# openfc.net
KiCad netlist of a schematic drawn in EAGLE
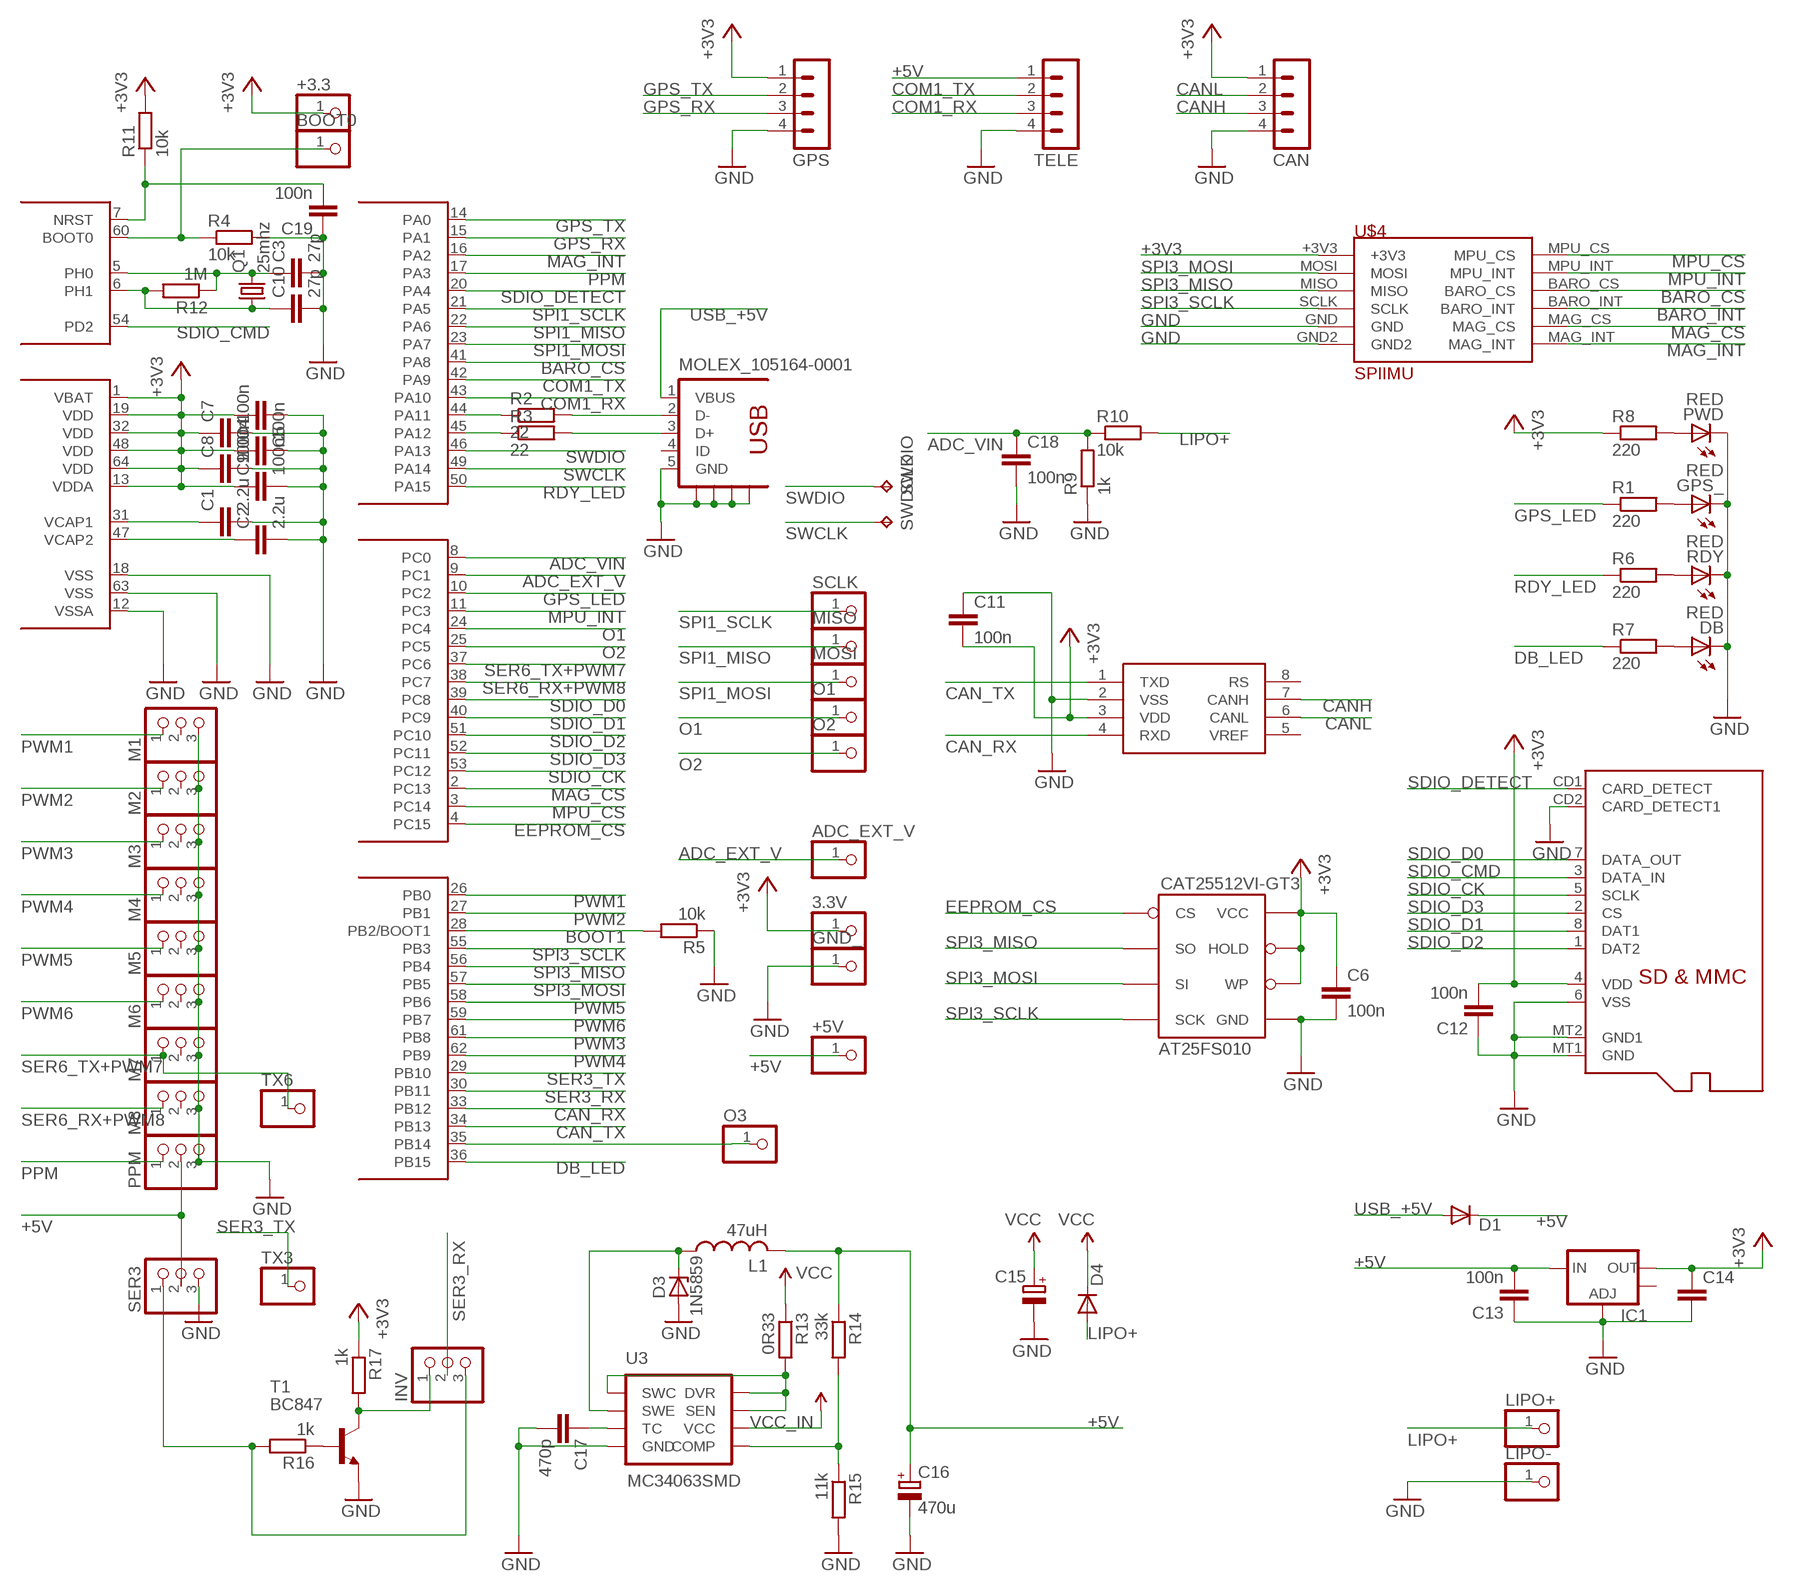
[diagram p0: schematic, sheet 1]

(export (version "E")
  (design (tool "Eeschema 10.0.6"))
  (components
    (comp (ref "+3.3")
      (value "PINHD-1X1")
      (footprint "eagle-import:1X01")
      (libsource (lib "eagle-import") (part "PINHD-1X1"))
    )
    (comp (ref "+5V")
      (value "PINHD-1X1")
      (footprint "eagle-import:1X01")
      (libsource (lib "eagle-import") (part "PINHD-1X1"))
    )
    (comp (ref "3.3V")
      (value "PINHD-1X1")
      (footprint "eagle-import:1X01")
      (libsource (lib "eagle-import") (part "PINHD-1X1"))
    )
    (comp (ref "ADC_EXT_V")
      (value "PINHD-1X1")
      (footprint "eagle-import:1X01")
      (libsource (lib "eagle-import") (part "PINHD-1X1"))
    )
    (comp (ref "BOOT0")
      (value "PINHD-1X1")
      (footprint "eagle-import:1X01")
      (libsource (lib "eagle-import") (part "PINHD-1X1"))
    )
    (comp (ref "C1")
      (value "2.2u")
      (footprint "eagle-import:C0603")
      (libsource (lib "eagle-import") (part "C-EUC0603"))
    )
    (comp (ref "C2")
      (value "2.2u")
      (footprint "eagle-import:C0603")
      (libsource (lib "eagle-import") (part "C-EUC0603"))
    )
    (comp (ref "C3")
      (value "27p")
      (footprint "eagle-import:C0603")
      (libsource (lib "eagle-import") (part "C-EUC0603"))
    )
    (comp (ref "C4")
      (value "100n")
      (footprint "eagle-import:C0603")
      (libsource (lib "eagle-import") (part "C-EUC0603"))
    )
    (comp (ref "C5")
      (value "100n")
      (footprint "eagle-import:C0603")
      (libsource (lib "eagle-import") (part "C-EUC0603"))
    )
    (comp (ref "C6")
      (value "100n")
      (footprint "eagle-import:C0603")
      (libsource (lib "eagle-import") (part "C-EUC0603"))
    )
    (comp (ref "C7")
      (value "100n")
      (footprint "eagle-import:C0603")
      (libsource (lib "eagle-import") (part "C-EUC0603"))
    )
    (comp (ref "C8")
      (value "100n")
      (footprint "eagle-import:C0603")
      (libsource (lib "eagle-import") (part "C-EUC0603"))
    )
    (comp (ref "C9")
      (value "100n")
      (footprint "eagle-import:C0603")
      (libsource (lib "eagle-import") (part "C-EUC0603"))
    )
    (comp (ref "C10")
      (value "27p")
      (footprint "eagle-import:C0603")
      (libsource (lib "eagle-import") (part "C-EUC0603"))
    )
    (comp (ref "C11")
      (value "100n")
      (footprint "eagle-import:C0603")
      (libsource (lib "eagle-import") (part "C-EUC0603"))
    )
    (comp (ref "C12")
      (value "100n")
      (footprint "eagle-import:C0603")
      (libsource (lib "eagle-import") (part "C-EUC0603"))
    )
    (comp (ref "C13")
      (value "100n")
      (footprint "eagle-import:C0603")
      (libsource (lib "eagle-import") (part "C-EUC0603"))
    )
    (comp (ref "C14")
      (value "C-EUC1206")
      (footprint "eagle-import:C1206")
      (libsource (lib "eagle-import") (part "C-EUC1206"))
    )
    (comp (ref "C15")
      (value "CPOL-EUB/3528-21R")
      (footprint "eagle-import:B_3528-21R")
      (libsource (lib "eagle-import") (part "CPOL-EUB/3528-21R"))
    )
    (comp (ref "C16")
      (value "470u")
      (footprint "eagle-import:B_3528-21R")
      (libsource (lib "eagle-import") (part "CPOL-EUB/3528-21R"))
    )
    (comp (ref "C17")
      (value "470p")
      (footprint "eagle-import:C0603")
      (libsource (lib "eagle-import") (part "C-EUC0603"))
    )
    (comp (ref "C18")
      (value "100n")
      (footprint "eagle-import:C0603")
      (libsource (lib "eagle-import") (part "C-EUC0603"))
    )
    (comp (ref "C19")
      (value "100n")
      (footprint "eagle-import:C0603")
      (libsource (lib "eagle-import") (part "C-EUC0603"))
    )
    (comp (ref "CAN")
      (value "MA04-1")
      (footprint "eagle-import:MA04-1")
      (fields (field (name "OC_FARNELL") "unknown") (field (name "OC_NEWARK") "unknown"))
      (libsource (lib "eagle-import") (part "MA04-1"))
    )
    (comp (ref "CAT25512VI-GT3")
      (value "AT25FS010")
      (footprint "eagle-import:SO08WIDE")
      (libsource (lib "eagle-import") (part "AT25FS010"))
    )
    (comp (ref "D1")
      (value "DIODE-SMB")
      (footprint "eagle-import:SMB")
      (libsource (lib "eagle-import") (part "DIODE-SMB"))
    )
    (comp (ref "D3")
      (value "1N5859")
      (footprint "eagle-import:SMB")
      (libsource (lib "eagle-import") (part "ZENER-DIODESMB"))
    )
    (comp (ref "D4")
      (value "DIODE-SMB")
      (footprint "eagle-import:SMB")
      (libsource (lib "eagle-import") (part "DIODE-SMB"))
    )
    (comp (ref "DB")
      (value "RED")
      (footprint "eagle-import:LED-0603")
      (fields (field (name "PROD_ID") "DIO-00819"))
      (libsource (lib "eagle-import") (part "LED-RED0603"))
    )
    (comp (ref "GND_")
      (value "PINHD-1X1")
      (footprint "eagle-import:1X01")
      (libsource (lib "eagle-import") (part "PINHD-1X1"))
    )
    (comp (ref "GPS")
      (value "MA04-1")
      (footprint "eagle-import:MA04-1")
      (libsource (lib "eagle-import") (part "MA04-1"))
    )
    (comp (ref "GPS_")
      (value "RED")
      (footprint "eagle-import:LED-0603")
      (fields (field (name "PROD_ID") "DIO-00819"))
      (libsource (lib "eagle-import") (part "LED-RED0603"))
    )
    (comp (ref "IC1")
      (value "V_REG_LM1117SOT223")
      (footprint "eagle-import:SOT223")
      (libsource (lib "eagle-import") (part "V_REG_LM1117SOT223"))
    )
    (comp (ref "INV")
      (value "PINHD-1X3")
      (footprint "eagle-import:1X03")
      (libsource (lib "eagle-import") (part "PINHD-1X3"))
    )
    (comp (ref "L1")
      (value "47uH")
      (footprint "eagle-import:L1812")
      (libsource (lib "eagle-import") (part "L-USL1812"))
    )
    (comp (ref "LIPO+")
      (value "PINHD-1X1")
      (footprint "eagle-import:1X01")
      (libsource (lib "eagle-import") (part "PINHD-1X1"))
    )
    (comp (ref "LIPO-")
      (value "PINHD-1X1")
      (footprint "eagle-import:1X01")
      (libsource (lib "eagle-import") (part "PINHD-1X1"))
    )
    (comp (ref "M1")
      (value "PINHD-1X3")
      (footprint "eagle-import:1X03")
      (libsource (lib "eagle-import") (part "PINHD-1X3"))
    )
    (comp (ref "M2")
      (value "PINHD-1X3")
      (footprint "eagle-import:1X03")
      (libsource (lib "eagle-import") (part "PINHD-1X3"))
    )
    (comp (ref "M3")
      (value "PINHD-1X3")
      (footprint "eagle-import:1X03")
      (libsource (lib "eagle-import") (part "PINHD-1X3"))
    )
    (comp (ref "M4")
      (value "PINHD-1X3")
      (footprint "eagle-import:1X03")
      (libsource (lib "eagle-import") (part "PINHD-1X3"))
    )
    (comp (ref "M5")
      (value "PINHD-1X3")
      (footprint "eagle-import:1X03")
      (libsource (lib "eagle-import") (part "PINHD-1X3"))
    )
    (comp (ref "M6")
      (value "PINHD-1X3")
      (footprint "eagle-import:1X03")
      (libsource (lib "eagle-import") (part "PINHD-1X3"))
    )
    (comp (ref "M7")
      (value "PINHD-1X3")
      (footprint "eagle-import:1X03")
      (libsource (lib "eagle-import") (part "PINHD-1X3"))
    )
    (comp (ref "M8")
      (value "PINHD-1X3")
      (footprint "eagle-import:1X03")
      (libsource (lib "eagle-import") (part "PINHD-1X3"))
    )
    (comp (ref "MISO")
      (value "PINHD-1X1")
      (footprint "eagle-import:1X01")
      (libsource (lib "eagle-import") (part "PINHD-1X1"))
    )
    (comp (ref "MOLEX_47334-0001")
      (value "MICROSD")
      (footprint "eagle-import:MICROSD")
      (libsource (lib "eagle-import") (part "MICROSD"))
    )
    (comp (ref "MOLEX_105164-0001")
      (value "USB-5P")
      (footprint "eagle-import:USB-MINI-B")
      (libsource (lib "eagle-import") (part "USB-5P"))
    )
    (comp (ref "MOSI")
      (value "PINHD-1X1")
      (footprint "eagle-import:1X01")
      (libsource (lib "eagle-import") (part "PINHD-1X1"))
    )
    (comp (ref "O1")
      (value "PINHD-1X1")
      (footprint "eagle-import:1X01")
      (libsource (lib "eagle-import") (part "PINHD-1X1"))
    )
    (comp (ref "O2")
      (value "PINHD-1X1")
      (footprint "eagle-import:1X01")
      (libsource (lib "eagle-import") (part "PINHD-1X1"))
    )
    (comp (ref "O3")
      (value "PINHD-1X1")
      (footprint "eagle-import:1X01")
      (libsource (lib "eagle-import") (part "PINHD-1X1"))
    )
    (comp (ref "PPM")
      (value "PINHD-1X3")
      (footprint "eagle-import:1X03")
      (libsource (lib "eagle-import") (part "PINHD-1X3"))
    )
    (comp (ref "PWD")
      (value "RED")
      (footprint "eagle-import:LED-0603")
      (fields (field (name "PROD_ID") "DIO-00819"))
      (libsource (lib "eagle-import") (part "LED-RED0603"))
    )
    (comp (ref "Q1")
      (value "25mhz")
      (footprint "eagle-import:CTS406")
      (fields (field (name "OC_FARNELL") "unknown"))
      (libsource (lib "eagle-import") (part "CRYSTALCTS406"))
    )
    (comp (ref "R1")
      (value "220")
      (footprint "eagle-import:R0603")
      (libsource (lib "eagle-import") (part "R-EU_R0603"))
    )
    (comp (ref "R2")
      (value "22")
      (footprint "eagle-import:R0603")
      (libsource (lib "eagle-import") (part "R-EU_R0603"))
    )
    (comp (ref "R3")
      (value "22")
      (footprint "eagle-import:R0603")
      (libsource (lib "eagle-import") (part "R-EU_R0603"))
    )
    (comp (ref "R4")
      (value "10k")
      (footprint "eagle-import:R0603")
      (libsource (lib "eagle-import") (part "R-EU_R0603"))
    )
    (comp (ref "R5")
      (value "10k")
      (footprint "eagle-import:R0603")
      (libsource (lib "eagle-import") (part "R-EU_R0603"))
    )
    (comp (ref "R6")
      (value "220")
      (footprint "eagle-import:R0603")
      (libsource (lib "eagle-import") (part "R-EU_R0603"))
    )
    (comp (ref "R7")
      (value "220")
      (footprint "eagle-import:R0603")
      (libsource (lib "eagle-import") (part "R-EU_R0603"))
    )
    (comp (ref "R8")
      (value "220")
      (footprint "eagle-import:R0603")
      (libsource (lib "eagle-import") (part "R-EU_R0603"))
    )
    (comp (ref "R9")
      (value "1k")
      (footprint "eagle-import:R0603")
      (libsource (lib "eagle-import") (part "R-EU_R0603"))
    )
    (comp (ref "R10")
      (value "10k")
      (footprint "eagle-import:R0603")
      (libsource (lib "eagle-import") (part "R-EU_R0603"))
    )
    (comp (ref "R11")
      (value "10k")
      (footprint "eagle-import:R0603")
      (libsource (lib "eagle-import") (part "R-EU_R0603"))
    )
    (comp (ref "R12")
      (value "1M")
      (footprint "eagle-import:R0603")
      (libsource (lib "eagle-import") (part "R-EU_R0603"))
    )
    (comp (ref "R13")
      (value "0R33")
      (footprint "eagle-import:R0603")
      (libsource (lib "eagle-import") (part "R-EU_R0603"))
    )
    (comp (ref "R14")
      (value "33k")
      (footprint "eagle-import:R0603")
      (libsource (lib "eagle-import") (part "R-EU_R0603"))
    )
    (comp (ref "R15")
      (value "11k")
      (footprint "eagle-import:R0603")
      (libsource (lib "eagle-import") (part "R-EU_R0603"))
    )
    (comp (ref "R16")
      (value "1k")
      (footprint "eagle-import:R0603")
      (libsource (lib "eagle-import") (part "R-EU_R0603"))
    )
    (comp (ref "R17")
      (value "1k")
      (footprint "eagle-import:R0603")
      (libsource (lib "eagle-import") (part "R-EU_R0603"))
    )
    (comp (ref "RDY")
      (value "RED")
      (footprint "eagle-import:LED-0603")
      (fields (field (name "PROD_ID") "DIO-00819"))
      (libsource (lib "eagle-import") (part "LED-RED0603"))
    )
    (comp (ref "SCLK")
      (value "PINHD-1X1")
      (footprint "eagle-import:1X01")
      (libsource (lib "eagle-import") (part "PINHD-1X1"))
    )
    (comp (ref "SER3")
      (value "PINHD-1X3")
      (footprint "eagle-import:1X03")
      (libsource (lib "eagle-import") (part "PINHD-1X3"))
    )
    (comp (ref "SWDCLK")
      (value "TPTP14SQ")
      (footprint "eagle-import:TP14SQ")
      (libsource (lib "eagle-import") (part "TPTP14SQ"))
    )
    (comp (ref "SWDIO")
      (value "TPTP14SQ")
      (footprint "eagle-import:TP14SQ")
      (libsource (lib "eagle-import") (part "TPTP14SQ"))
    )
    (comp (ref "T1")
      (value "BC847")
      (footprint "eagle-import:SOT23")
      (libsource (lib "eagle-import") (part "BC847"))
    )
    (comp (ref "TELE")
      (value "MA04-1")
      (footprint "eagle-import:MA04-1")
      (libsource (lib "eagle-import") (part "MA04-1"))
    )
    (comp (ref "TX3")
      (value "PINHD-1X1")
      (footprint "eagle-import:1X01")
      (libsource (lib "eagle-import") (part "PINHD-1X1"))
    )
    (comp (ref "TX6")
      (value "PINHD-1X1")
      (footprint "eagle-import:1X01")
      (libsource (lib "eagle-import") (part "PINHD-1X1"))
    )
    (comp (ref "U$4")
      (value "SPIIMU")
      (footprint "eagle-import:SPIIMU")
      (libsource (lib "eagle-import") (part "SPIIMU"))
    )
    (comp (ref "U1")
      (value "STM32F4-64")
      (footprint "eagle-import:SQFP-S-10X10-64")
      (libsource (lib "eagle-import") (part "STM32F4-64"))
    )
    (comp (ref "U3")
      (value "MC34063SMD")
      (footprint "eagle-import:SO08")
      (libsource (lib "eagle-import") (part "MC34063SMD"))
    )
    (comp (ref "U4")
      (value "MCP2551")
      (footprint "eagle-import:SO08")
      (libsource (lib "eagle-import") (part "MCP2551"))
    )
  )
  (nets
    (net (code "1") (name "+3V3") (class "Default")
      (node (ref "+3.3") (pin "1") (pinfunction "1_1") (pintype "passive"))
      (node (ref "3.3V") (pin "1") (pinfunction "1_1") (pintype "passive"))
      (node (ref "C11") (pin "2") (pinfunction "2_2") (pintype "passive"))
      (node (ref "C12") (pin "2") (pinfunction "2_2") (pintype "passive"))
      (node (ref "C14") (pin "1") (pinfunction "1_1") (pintype "passive"))
      (node (ref "C4") (pin "1") (pinfunction "1_1") (pintype "passive"))
      (node (ref "C5") (pin "2") (pinfunction "2_2") (pintype "passive"))
      (node (ref "C6") (pin "1") (pinfunction "1_1") (pintype "passive"))
      (node (ref "C7") (pin "1") (pinfunction "1_1") (pintype "passive"))
      (node (ref "C8") (pin "1") (pinfunction "1_1") (pintype "passive"))
      (node (ref "C9") (pin "1") (pinfunction "1_1") (pintype "passive"))
      (node (ref "CAN") (pin "1") (pinfunction "1_1") (pintype "passive"))
      (node (ref "CAT25512VI-GT3") (pin "3") (pinfunction "WP_3") (pintype "bidirectional"))
      (node (ref "CAT25512VI-GT3") (pin "7") (pinfunction "HOLD_7") (pintype "bidirectional"))
      (node (ref "CAT25512VI-GT3") (pin "8") (pinfunction "VCC_8") (pintype "bidirectional"))
      (node (ref "GPS") (pin "1") (pinfunction "1_1") (pintype "passive"))
      (node (ref "IC1") (pin "2") (pinfunction "OUT_2") (pintype "output"))
      (node (ref "MOLEX_47334-0001") (pin "4") (pinfunction "VDD_4") (pintype "power_in"))
      (node (ref "R11") (pin "2") (pinfunction "2_2") (pintype "passive"))
      (node (ref "R17") (pin "1") (pinfunction "1_1") (pintype "passive"))
      (node (ref "R8") (pin "1") (pinfunction "1_1") (pintype "passive"))
      (node (ref "U$4") (pin "+3V3") (pinfunction "+3V3_+3V3") (pintype "power_in"))
      (node (ref "U1") (pin "1") (pinfunction "VBAT_1") (pintype "power_in"))
      (node (ref "U1") (pin "13") (pinfunction "VDDA_13") (pintype "power_in"))
      (node (ref "U1") (pin "19") (pinfunction "VDD_19") (pintype "power_in"))
      (node (ref "U1") (pin "32") (pinfunction "VDD_32") (pintype "power_in"))
      (node (ref "U1") (pin "48") (pinfunction "VDD_48") (pintype "power_in"))
      (node (ref "U1") (pin "64") (pinfunction "VDD_64") (pintype "power_in"))
      (node (ref "U4") (pin "3") (pinfunction "VDD_3") (pintype "bidirectional"))
    )
    (net (code "2") (name "/+5V") (class "Default")
      (node (ref "+5V") (pin "1") (pinfunction "1_1") (pintype "passive"))
      (node (ref "C13") (pin "2") (pinfunction "2_2") (pintype "passive"))
      (node (ref "C16") (pin "+") (pinfunction "+_+") (pintype "passive"))
      (node (ref "D1") (pin "C") (pinfunction "C_C") (pintype "passive"))
      (node (ref "IC1") (pin "3") (pinfunction "IN_3") (pintype "input"))
      (node (ref "L1") (pin "2") (pinfunction "2_2") (pintype "passive"))
      (node (ref "PPM") (pin "2") (pinfunction "2_2") (pintype "passive"))
      (node (ref "R14") (pin "1") (pinfunction "1_1") (pintype "passive"))
      (node (ref "SER3") (pin "2") (pinfunction "2_2") (pintype "passive"))
      (node (ref "TELE") (pin "1") (pinfunction "1_1") (pintype "passive"))
    )
    (net (code "3") (name "/ADC_EXT_V") (class "Default")
      (node (ref "ADC_EXT_V") (pin "1") (pinfunction "1_1") (pintype "passive"))
      (node (ref "U1") (pin "9") (pinfunction "PC1_9") (pintype "bidirectional"))
    )
    (net (code "4") (name "/ADC_VIN") (class "Default")
      (node (ref "C18") (pin "1") (pinfunction "1_1") (pintype "passive"))
      (node (ref "R10") (pin "1") (pinfunction "1_1") (pintype "passive"))
      (node (ref "R9") (pin "2") (pinfunction "2_2") (pintype "passive"))
      (node (ref "U1") (pin "8") (pinfunction "PC0_8") (pintype "bidirectional"))
    )
    (net (code "5") (name "/BARO_CS") (class "Default")
      (node (ref "U$4") (pin "BARO_CS") (pinfunction "BARO_CS_BARO_CS") (pintype "bidirectional"))
      (node (ref "U1") (pin "41") (pinfunction "PA8_41") (pintype "bidirectional"))
    )
    (net (code "6") (name "/BARO_INT") (class "Default")
      (node (ref "U$4") (pin "BARO_INT") (pinfunction "BARO_INT_BARO_INT") (pintype "bidirectional"))
    )
    (net (code "7") (name "/BOOT1") (class "Default")
      (node (ref "R5") (pin "2") (pinfunction "2_2") (pintype "passive"))
      (node (ref "U1") (pin "28") (pinfunction "PB2/BOOT1_28") (pintype "bidirectional"))
    )
    (net (code "8") (name "/CANH") (class "Default")
      (node (ref "CAN") (pin "3") (pinfunction "3_3") (pintype "passive"))
      (node (ref "U4") (pin "7") (pinfunction "CANH_7") (pintype "bidirectional"))
    )
    (net (code "9") (name "/CANL") (class "Default")
      (node (ref "CAN") (pin "2") (pinfunction "2_2") (pintype "passive"))
      (node (ref "U4") (pin "6") (pinfunction "CANL_6") (pintype "bidirectional"))
    )
    (net (code "10") (name "/CAN_RX") (class "Default")
      (node (ref "U1") (pin "33") (pinfunction "PB12_33") (pintype "bidirectional"))
      (node (ref "U4") (pin "4") (pinfunction "RXD_4") (pintype "bidirectional"))
    )
    (net (code "11") (name "/CAN_TX") (class "Default")
      (node (ref "U1") (pin "34") (pinfunction "PB13_34") (pintype "bidirectional"))
      (node (ref "U4") (pin "1") (pinfunction "TXD_1") (pintype "bidirectional"))
    )
    (net (code "12") (name "/COM1_RX") (class "Default")
      (node (ref "TELE") (pin "3") (pinfunction "3_3") (pintype "passive"))
      (node (ref "U1") (pin "43") (pinfunction "PA10_43") (pintype "bidirectional"))
    )
    (net (code "13") (name "/COM1_TX") (class "Default")
      (node (ref "TELE") (pin "2") (pinfunction "2_2") (pintype "passive"))
      (node (ref "U1") (pin "42") (pinfunction "PA9_42") (pintype "bidirectional"))
    )
    (net (code "14") (name "/DB_LED") (class "Default")
      (node (ref "R7") (pin "1") (pinfunction "1_1") (pintype "passive"))
      (node (ref "U1") (pin "36") (pinfunction "PB15_36") (pintype "bidirectional"))
    )
    (net (code "15") (name "/EEPROM_CS") (class "Default")
      (node (ref "CAT25512VI-GT3") (pin "1") (pinfunction "CS_1") (pintype "bidirectional"))
      (node (ref "U1") (pin "4") (pinfunction "PC15_4") (pintype "bidirectional"))
    )
    (net (code "16") (name "/GPS_LED") (class "Default")
      (node (ref "R1") (pin "1") (pinfunction "1_1") (pintype "passive"))
      (node (ref "U1") (pin "10") (pinfunction "PC2_10") (pintype "bidirectional"))
    )
    (net (code "17") (name "/GPS_RX") (class "Default")
      (node (ref "GPS") (pin "3") (pinfunction "3_3") (pintype "passive"))
      (node (ref "U1") (pin "15") (pinfunction "PA1_15") (pintype "bidirectional"))
    )
    (net (code "18") (name "/GPS_TX") (class "Default")
      (node (ref "GPS") (pin "2") (pinfunction "2_2") (pintype "passive"))
      (node (ref "U1") (pin "14") (pinfunction "PA0_14") (pintype "bidirectional"))
    )
    (net (code "19") (name "/LIPO+") (class "Default")
      (node (ref "D4") (pin "A") (pinfunction "A_A") (pintype "passive"))
      (node (ref "LIPO+") (pin "1") (pinfunction "1_1") (pintype "passive"))
      (node (ref "R10") (pin "2") (pinfunction "2_2") (pintype "passive"))
    )
    (net (code "20") (name "/MAG_CS") (class "Default")
      (node (ref "U$4") (pin "MAG_CS") (pinfunction "MAG_CS_MAG_CS") (pintype "bidirectional"))
      (node (ref "U1") (pin "2") (pinfunction "PC13_2") (pintype "bidirectional"))
    )
    (net (code "21") (name "/MAG_INT") (class "Default")
      (node (ref "U$4") (pin "MAG_INT") (pinfunction "MAG_INT_MAG_INT") (pintype "bidirectional"))
      (node (ref "U1") (pin "16") (pinfunction "PA2_16") (pintype "bidirectional"))
    )
    (net (code "22") (name "/MPU_CS") (class "Default")
      (node (ref "U$4") (pin "MPU_CS") (pinfunction "MPU_CS_MPU_CS") (pintype "bidirectional"))
      (node (ref "U1") (pin "3") (pinfunction "PC14_3") (pintype "bidirectional"))
    )
    (net (code "23") (name "/MPU_INT") (class "Default")
      (node (ref "U$4") (pin "MPU_INT") (pinfunction "MPU_INT_MPU_INT") (pintype "bidirectional"))
      (node (ref "U1") (pin "11") (pinfunction "PC3_11") (pintype "bidirectional"))
    )
    (net (code "24") (name "/O1") (class "Default")
      (node (ref "O1") (pin "1") (pinfunction "1_1") (pintype "passive"))
      (node (ref "U1") (pin "24") (pinfunction "PC4_24") (pintype "bidirectional"))
    )
    (net (code "25") (name "/O2") (class "Default")
      (node (ref "O2") (pin "1") (pinfunction "1_1") (pintype "passive"))
      (node (ref "U1") (pin "25") (pinfunction "PC5_25") (pintype "bidirectional"))
    )
    (net (code "26") (name "/PPM") (class "Default")
      (node (ref "PPM") (pin "1") (pinfunction "1_1") (pintype "passive"))
      (node (ref "U1") (pin "17") (pinfunction "PA3_17") (pintype "bidirectional"))
    )
    (net (code "27") (name "/PWM1") (class "Default")
      (node (ref "M1") (pin "1") (pinfunction "1_1") (pintype "passive"))
      (node (ref "U1") (pin "26") (pinfunction "PB0_26") (pintype "bidirectional"))
    )
    (net (code "28") (name "/PWM2") (class "Default")
      (node (ref "M2") (pin "1") (pinfunction "1_1") (pintype "passive"))
      (node (ref "U1") (pin "27") (pinfunction "PB1_27") (pintype "bidirectional"))
    )
    (net (code "29") (name "/PWM3") (class "Default")
      (node (ref "M3") (pin "1") (pinfunction "1_1") (pintype "passive"))
      (node (ref "U1") (pin "61") (pinfunction "PB8_61") (pintype "bidirectional"))
    )
    (net (code "30") (name "/PWM4") (class "Default")
      (node (ref "M4") (pin "1") (pinfunction "1_1") (pintype "passive"))
      (node (ref "U1") (pin "62") (pinfunction "PB9_62") (pintype "bidirectional"))
    )
    (net (code "31") (name "/PWM5") (class "Default")
      (node (ref "M5") (pin "1") (pinfunction "1_1") (pintype "passive"))
      (node (ref "U1") (pin "58") (pinfunction "PB6_58") (pintype "bidirectional"))
    )
    (net (code "32") (name "/PWM6") (class "Default")
      (node (ref "M6") (pin "1") (pinfunction "1_1") (pintype "passive"))
      (node (ref "U1") (pin "59") (pinfunction "PB7_59") (pintype "bidirectional"))
    )
    (net (code "33") (name "/RDY_LED") (class "Default")
      (node (ref "R6") (pin "1") (pinfunction "1_1") (pintype "passive"))
      (node (ref "U1") (pin "50") (pinfunction "PA15_50") (pintype "bidirectional"))
    )
    (net (code "34") (name "/SDIO_CK") (class "Default")
      (node (ref "MOLEX_47334-0001") (pin "5") (pinfunction "SCLK_5") (pintype "input"))
      (node (ref "U1") (pin "53") (pinfunction "PC12_53") (pintype "bidirectional"))
    )
    (net (code "35") (name "/SDIO_CMD") (class "Default")
      (node (ref "MOLEX_47334-0001") (pin "3") (pinfunction "DATA_IN_3") (pintype "input"))
      (node (ref "U1") (pin "54") (pinfunction "PD2_54") (pintype "bidirectional"))
    )
    (net (code "36") (name "/SDIO_D0") (class "Default")
      (node (ref "MOLEX_47334-0001") (pin "7") (pinfunction "DATA_OUT_7") (pintype "output"))
      (node (ref "U1") (pin "39") (pinfunction "PC8_39") (pintype "bidirectional"))
    )
    (net (code "37") (name "/SDIO_D1") (class "Default")
      (node (ref "MOLEX_47334-0001") (pin "8") (pinfunction "DAT1_8") (pintype "bidirectional"))
      (node (ref "U1") (pin "40") (pinfunction "PC9_40") (pintype "bidirectional"))
    )
    (net (code "38") (name "/SDIO_D2") (class "Default")
      (node (ref "MOLEX_47334-0001") (pin "1") (pinfunction "DAT2_1") (pintype "bidirectional"))
      (node (ref "U1") (pin "51") (pinfunction "PC10_51") (pintype "bidirectional"))
    )
    (net (code "39") (name "/SDIO_D3") (class "Default")
      (node (ref "MOLEX_47334-0001") (pin "2") (pinfunction "CS_2") (pintype "input"))
      (node (ref "U1") (pin "52") (pinfunction "PC11_52") (pintype "bidirectional"))
    )
    (net (code "40") (name "/SDIO_DETECT") (class "Default")
      (node (ref "MOLEX_47334-0001") (pin "CD1") (pinfunction "CARD_DETECT_CD1") (pintype "passive"))
      (node (ref "U1") (pin "20") (pinfunction "PA4_20") (pintype "bidirectional"))
    )
    (net (code "41") (name "/SER3_RX") (class "Default")
      (node (ref "INV") (pin "2") (pinfunction "2_2") (pintype "passive"))
      (node (ref "U1") (pin "30") (pinfunction "PB11_30") (pintype "bidirectional"))
    )
    (net (code "42") (name "/SER3_TX") (class "Default")
      (node (ref "TX3") (pin "1") (pinfunction "1_1") (pintype "passive"))
      (node (ref "U1") (pin "29") (pinfunction "PB10_29") (pintype "bidirectional"))
    )
    (net (code "43") (name "/SER6_RX+PWM8") (class "Default")
      (node (ref "M8") (pin "1") (pinfunction "1_1") (pintype "passive"))
      (node (ref "U1") (pin "38") (pinfunction "PC7_38") (pintype "bidirectional"))
    )
    (net (code "44") (name "/SER6_TX+PWM7") (class "Default")
      (node (ref "M7") (pin "1") (pinfunction "1_1") (pintype "passive"))
      (node (ref "TX6") (pin "1") (pinfunction "1_1") (pintype "passive"))
      (node (ref "U1") (pin "37") (pinfunction "PC6_37") (pintype "bidirectional"))
    )
    (net (code "45") (name "/SPI1_MISO") (class "Default")
      (node (ref "MISO") (pin "1") (pinfunction "1_1") (pintype "passive"))
      (node (ref "U1") (pin "22") (pinfunction "PA6_22") (pintype "bidirectional"))
    )
    (net (code "46") (name "/SPI1_MOSI") (class "Default")
      (node (ref "MOSI") (pin "1") (pinfunction "1_1") (pintype "passive"))
      (node (ref "U1") (pin "23") (pinfunction "PA7_23") (pintype "bidirectional"))
    )
    (net (code "47") (name "/SPI1_SCLK") (class "Default")
      (node (ref "SCLK") (pin "1") (pinfunction "1_1") (pintype "passive"))
      (node (ref "U1") (pin "21") (pinfunction "PA5_21") (pintype "bidirectional"))
    )
    (net (code "48") (name "/SPI3_MISO") (class "Default")
      (node (ref "CAT25512VI-GT3") (pin "2") (pinfunction "SO_2") (pintype "bidirectional"))
      (node (ref "U$4") (pin "MISO") (pinfunction "MISO_MISO") (pintype "bidirectional"))
      (node (ref "U1") (pin "56") (pinfunction "PB4_56") (pintype "bidirectional"))
    )
    (net (code "49") (name "/SPI3_MOSI") (class "Default")
      (node (ref "CAT25512VI-GT3") (pin "5") (pinfunction "SI_5") (pintype "bidirectional"))
      (node (ref "U$4") (pin "MOSI") (pinfunction "MOSI_MOSI") (pintype "bidirectional"))
      (node (ref "U1") (pin "57") (pinfunction "PB5_57") (pintype "bidirectional"))
    )
    (net (code "50") (name "/SPI3_SCLK") (class "Default")
      (node (ref "CAT25512VI-GT3") (pin "6") (pinfunction "SCK_6") (pintype "bidirectional"))
      (node (ref "U$4") (pin "SCLK") (pinfunction "SCLK_SCLK") (pintype "bidirectional"))
      (node (ref "U1") (pin "55") (pinfunction "PB3_55") (pintype "bidirectional"))
    )
    (net (code "51") (name "/SWCLK") (class "Default")
      (node (ref "SWDCLK") (pin "TP") (pinfunction "TP_TP") (pintype "input"))
      (node (ref "U1") (pin "49") (pinfunction "PA14_49") (pintype "bidirectional"))
    )
    (net (code "52") (name "/SWDIO") (class "Default")
      (node (ref "SWDIO") (pin "TP") (pinfunction "TP_TP") (pintype "input"))
      (node (ref "U1") (pin "46") (pinfunction "PA13_46") (pintype "bidirectional"))
    )
    (net (code "53") (name "/USB_+5V") (class "Default")
      (node (ref "D1") (pin "A") (pinfunction "A_A") (pintype "passive"))
      (node (ref "MOLEX_105164-0001") (pin "1") (pinfunction "VBUS_1") (pintype "passive"))
    )
    (net (code "54") (name "GND") (class "Default")
      (node (ref "C1") (pin "2") (pinfunction "2_2") (pintype "passive"))
      (node (ref "C10") (pin "2") (pinfunction "2_2") (pintype "passive"))
      (node (ref "C11") (pin "1") (pinfunction "1_1") (pintype "passive"))
      (node (ref "C12") (pin "1") (pinfunction "1_1") (pintype "passive"))
      (node (ref "C13") (pin "1") (pinfunction "1_1") (pintype "passive"))
      (node (ref "C14") (pin "2") (pinfunction "2_2") (pintype "passive"))
      (node (ref "C15") (pin "-") (pinfunction "-_-") (pintype "passive"))
      (node (ref "C16") (pin "-") (pinfunction "-_-") (pintype "passive"))
      (node (ref "C17") (pin "2") (pinfunction "2_2") (pintype "passive"))
      (node (ref "C18") (pin "2") (pinfunction "2_2") (pintype "passive"))
      (node (ref "C19") (pin "1") (pinfunction "1_1") (pintype "passive"))
      (node (ref "C2") (pin "2") (pinfunction "2_2") (pintype "passive"))
      (node (ref "C3") (pin "2") (pinfunction "2_2") (pintype "passive"))
      (node (ref "C4") (pin "2") (pinfunction "2_2") (pintype "passive"))
      (node (ref "C5") (pin "1") (pinfunction "1_1") (pintype "passive"))
      (node (ref "C6") (pin "2") (pinfunction "2_2") (pintype "passive"))
      (node (ref "C7") (pin "2") (pinfunction "2_2") (pintype "passive"))
      (node (ref "C8") (pin "2") (pinfunction "2_2") (pintype "passive"))
      (node (ref "C9") (pin "2") (pinfunction "2_2") (pintype "passive"))
      (node (ref "CAN") (pin "4") (pinfunction "4_4") (pintype "passive"))
      (node (ref "CAT25512VI-GT3") (pin "4") (pinfunction "GND_4") (pintype "bidirectional"))
      (node (ref "D3") (pin "A") (pinfunction "A_A") (pintype "passive"))
      (node (ref "DB") (pin "C") (pinfunction "C_C") (pintype "passive"))
      (node (ref "GND_") (pin "1") (pinfunction "1_1") (pintype "passive"))
      (node (ref "GPS") (pin "4") (pinfunction "4_4") (pintype "passive"))
      (node (ref "GPS_") (pin "C") (pinfunction "C_C") (pintype "passive"))
      (node (ref "IC1") (pin "1") (pinfunction "ADJ_1") (pintype "input"))
      (node (ref "LIPO-") (pin "1") (pinfunction "1_1") (pintype "passive"))
      (node (ref "M1") (pin "3") (pinfunction "3_3") (pintype "passive"))
      (node (ref "M2") (pin "3") (pinfunction "3_3") (pintype "passive"))
      (node (ref "M3") (pin "3") (pinfunction "3_3") (pintype "passive"))
      (node (ref "M4") (pin "3") (pinfunction "3_3") (pintype "passive"))
      (node (ref "M5") (pin "3") (pinfunction "3_3") (pintype "passive"))
      (node (ref "M6") (pin "3") (pinfunction "3_3") (pintype "passive"))
      (node (ref "M7") (pin "3") (pinfunction "3_3") (pintype "passive"))
      (node (ref "M8") (pin "3") (pinfunction "3_3") (pintype "passive"))
      (node (ref "MOLEX_105164-0001") (pin "5") (pinfunction "GND_5") (pintype "passive"))
      (node (ref "MOLEX_105164-0001") (pin "S1") (pinfunction "S1_S1") (pintype "passive"))
      (node (ref "MOLEX_105164-0001") (pin "S2") (pinfunction "S2_S2") (pintype "passive"))
      (node (ref "MOLEX_105164-0001") (pin "S3") (pinfunction "S3_S3") (pintype "passive"))
      (node (ref "MOLEX_105164-0001") (pin "S4") (pinfunction "S4_S4") (pintype "passive"))
      (node (ref "MOLEX_47334-0001") (pin "6") (pinfunction "VSS_6") (pintype "power_in"))
      (node (ref "MOLEX_47334-0001") (pin "CD2") (pinfunction "CARD_DETECT1_CD2") (pintype "passive"))
      (node (ref "MOLEX_47334-0001") (pin "MT1") (pinfunction "GND_MT1") (pintype "power_in"))
      (node (ref "MOLEX_47334-0001") (pin "MT2") (pinfunction "GND1_MT2") (pintype "power_in"))
      (node (ref "PPM") (pin "3") (pinfunction "3_3") (pintype "passive"))
      (node (ref "PWD") (pin "C") (pinfunction "C_C") (pintype "passive"))
      (node (ref "R15") (pin "2") (pinfunction "2_2") (pintype "passive"))
      (node (ref "R4") (pin "2") (pinfunction "2_2") (pintype "passive"))
      (node (ref "R5") (pin "1") (pinfunction "1_1") (pintype "passive"))
      (node (ref "R9") (pin "1") (pinfunction "1_1") (pintype "passive"))
      (node (ref "RDY") (pin "C") (pinfunction "C_C") (pintype "passive"))
      (node (ref "SER3") (pin "3") (pinfunction "3_3") (pintype "passive"))
      (node (ref "T1") (pin "2") (pinfunction "E_2") (pintype "passive"))
      (node (ref "TELE") (pin "4") (pinfunction "4_4") (pintype "passive"))
      (node (ref "U$4") (pin "GND") (pinfunction "GND_GND") (pintype "power_in"))
      (node (ref "U$4") (pin "GND2") (pinfunction "GND2_GND2") (pintype "power_in"))
      (node (ref "U1") (pin "12") (pinfunction "VSSA_12") (pintype "power_in"))
      (node (ref "U1") (pin "18") (pinfunction "VSS_18") (pintype "power_in"))
      (node (ref "U1") (pin "63") (pinfunction "VSS_63") (pintype "power_in"))
      (node (ref "U3") (pin "4") (pinfunction "GND_4") (pintype "bidirectional"))
      (node (ref "U4") (pin "2") (pinfunction "VSS_2") (pintype "bidirectional"))
    )
    (net (code "55") (name "Net-(DB-PadA)") (class "Default")
      (node (ref "DB") (pin "A") (pinfunction "A_A") (pintype "passive"))
      (node (ref "R7") (pin "2") (pinfunction "2_2") (pintype "passive"))
    )
    (net (code "56") (name "Net-(GPS_-PadA)") (class "Default")
      (node (ref "GPS_") (pin "A") (pinfunction "A_A") (pintype "passive"))
      (node (ref "R1") (pin "2") (pinfunction "2_2") (pintype "passive"))
    )
    (net (code "57") (name "Net-(INV-Pad3)") (class "Default")
      (node (ref "INV") (pin "3") (pinfunction "3_3") (pintype "passive"))
      (node (ref "R16") (pin "2") (pinfunction "2_2") (pintype "passive"))
      (node (ref "SER3") (pin "1") (pinfunction "1_1") (pintype "passive"))
    )
    (net (code "58") (name "Net-(MOLEX_105164-0001-D+)") (class "Default")
      (node (ref "MOLEX_105164-0001") (pin "3") (pinfunction "D+_3") (pintype "passive"))
      (node (ref "R3") (pin "2") (pinfunction "2_2") (pintype "passive"))
    )
    (net (code "59") (name "Net-(MOLEX_105164-0001-D-)") (class "Default")
      (node (ref "MOLEX_105164-0001") (pin "2") (pinfunction "D-_2") (pintype "passive"))
      (node (ref "R2") (pin "2") (pinfunction "2_2") (pintype "passive"))
    )
    (net (code "60") (name "Net-(PWD-PadA)") (class "Default")
      (node (ref "PWD") (pin "A") (pinfunction "A_A") (pintype "passive"))
      (node (ref "R8") (pin "2") (pinfunction "2_2") (pintype "passive"))
    )
    (net (code "61") (name "Net-(Q1-2)") (class "Default")
      (node (ref "C3") (pin "1") (pinfunction "1_1") (pintype "passive"))
      (node (ref "Q1") (pin "3") (pinfunction "2_3") (pintype "passive"))
      (node (ref "R12") (pin "1") (pinfunction "1_1") (pintype "passive"))
      (node (ref "U1") (pin "5") (pinfunction "PH0_5") (pintype "bidirectional"))
    )
    (net (code "62") (name "Net-(R6-Pad2)") (class "Default")
      (node (ref "R6") (pin "2") (pinfunction "2_2") (pintype "passive"))
      (node (ref "RDY") (pin "A") (pinfunction "A_A") (pintype "passive"))
    )
    (net (code "63") (name "Net-(T1-B)") (class "Default")
      (node (ref "R16") (pin "1") (pinfunction "1_1") (pintype "passive"))
      (node (ref "T1") (pin "1") (pinfunction "B_1") (pintype "passive"))
    )
    (net (code "64") (name "Net-(T1-C)") (class "Default")
      (node (ref "INV") (pin "1") (pinfunction "1_1") (pintype "passive"))
      (node (ref "R17") (pin "2") (pinfunction "2_2") (pintype "passive"))
      (node (ref "T1") (pin "3") (pinfunction "C_3") (pintype "passive"))
    )
    (net (code "65") (name "Net-(U1A-VCAP1)") (class "Default")
      (node (ref "C1") (pin "1") (pinfunction "1_1") (pintype "passive"))
      (node (ref "U1") (pin "31") (pinfunction "VCAP1_31") (pintype "passive"))
    )
    (net (code "66") (name "Net-(U1A-VCAP2)") (class "Default")
      (node (ref "C2") (pin "1") (pinfunction "1_1") (pintype "passive"))
      (node (ref "U1") (pin "47") (pinfunction "VCAP2_47") (pintype "passive"))
    )
    (net (code "67") (name "Net-(U1B-PA11)") (class "Default")
      (node (ref "R2") (pin "1") (pinfunction "1_1") (pintype "passive"))
      (node (ref "U1") (pin "44") (pinfunction "PA11_44") (pintype "bidirectional"))
    )
    (net (code "68") (name "Net-(U1B-PA12)") (class "Default")
      (node (ref "R3") (pin "1") (pinfunction "1_1") (pintype "passive"))
      (node (ref "U1") (pin "45") (pinfunction "PA12_45") (pintype "bidirectional"))
    )
    (net (code "69") (name "Net-(U1C-PB14)") (class "Default")
      (node (ref "O3") (pin "1") (pinfunction "1_1") (pintype "passive"))
      (node (ref "U1") (pin "35") (pinfunction "PB14_35") (pintype "bidirectional"))
    )
    (net (code "70") (name "Net-(U1E-BOOT0)") (class "Default")
      (node (ref "BOOT0") (pin "1") (pinfunction "1_1") (pintype "passive"))
      (node (ref "R4") (pin "1") (pinfunction "1_1") (pintype "passive"))
      (node (ref "U1") (pin "60") (pinfunction "BOOT0_60") (pintype "bidirectional"))
    )
    (net (code "71") (name "Net-(U1E-NRST)") (class "Default")
      (node (ref "C19") (pin "2") (pinfunction "2_2") (pintype "passive"))
      (node (ref "R11") (pin "1") (pinfunction "1_1") (pintype "passive"))
      (node (ref "U1") (pin "7") (pinfunction "NRST_7") (pintype "bidirectional"))
    )
    (net (code "72") (name "Net-(U1E-PH1)") (class "Default")
      (node (ref "C10") (pin "1") (pinfunction "1_1") (pintype "passive"))
      (node (ref "Q1") (pin "1") (pinfunction "1_1") (pintype "passive"))
      (node (ref "R12") (pin "2") (pinfunction "2_2") (pintype "passive"))
      (node (ref "U1") (pin "6") (pinfunction "PH1_6") (pintype "bidirectional"))
    )
    (net (code "73") (name "Net-(U3-COMP)") (class "Default")
      (node (ref "R14") (pin "2") (pinfunction "2_2") (pintype "passive"))
      (node (ref "R15") (pin "1") (pinfunction "1_1") (pintype "passive"))
      (node (ref "U3") (pin "5") (pinfunction "COMP_5") (pintype "bidirectional"))
    )
    (net (code "74") (name "Net-(U3-DVR)") (class "Default")
      (node (ref "R13") (pin "2") (pinfunction "2_2") (pintype "passive"))
      (node (ref "U3") (pin "1") (pinfunction "SWC_1") (pintype "bidirectional"))
      (node (ref "U3") (pin "7") (pinfunction "SEN_7") (pintype "bidirectional"))
      (node (ref "U3") (pin "8") (pinfunction "DVR_8") (pintype "bidirectional"))
    )
    (net (code "75") (name "Net-(U3-SWE)") (class "Default")
      (node (ref "D3") (pin "C") (pinfunction "C_C") (pintype "passive"))
      (node (ref "L1") (pin "1") (pinfunction "1_1") (pintype "passive"))
      (node (ref "U3") (pin "2") (pinfunction "SWE_2") (pintype "bidirectional"))
    )
    (net (code "76") (name "Net-(U3-TC)") (class "Default")
      (node (ref "C17") (pin "1") (pinfunction "1_1") (pintype "passive"))
      (node (ref "U3") (pin "3") (pinfunction "TC_3") (pintype "bidirectional"))
    )
    (net (code "77") (name "VCC") (class "Default")
      (node (ref "C15") (pin "+") (pinfunction "+_+") (pintype "passive"))
      (node (ref "D4") (pin "C") (pinfunction "C_C") (pintype "passive"))
      (node (ref "R13") (pin "1") (pinfunction "1_1") (pintype "passive"))
      (node (ref "U3") (pin "6") (pinfunction "VCC_6") (pintype "bidirectional"))
    )
    (net (code "78") (name "unconnected-(IC1-OUT-Pad4)") (class "Default")
      (node (ref "IC1") (pin "4") (pinfunction "OUT_4") (pintype "output"))
    )
    (net (code "79") (name "unconnected-(M1-Pad2)") (class "Default")
      (node (ref "M1") (pin "2") (pinfunction "2_2") (pintype "passive"))
    )
    (net (code "80") (name "unconnected-(M2-Pad2)") (class "Default")
      (node (ref "M2") (pin "2") (pinfunction "2_2") (pintype "passive"))
    )
    (net (code "81") (name "unconnected-(M3-Pad2)") (class "Default")
      (node (ref "M3") (pin "2") (pinfunction "2_2") (pintype "passive"))
    )
    (net (code "82") (name "unconnected-(M4-Pad2)") (class "Default")
      (node (ref "M4") (pin "2") (pinfunction "2_2") (pintype "passive"))
    )
    (net (code "83") (name "unconnected-(M5-Pad2)") (class "Default")
      (node (ref "M5") (pin "2") (pinfunction "2_2") (pintype "passive"))
    )
    (net (code "84") (name "unconnected-(M6-Pad2)") (class "Default")
      (node (ref "M6") (pin "2") (pinfunction "2_2") (pintype "passive"))
    )
    (net (code "85") (name "unconnected-(M7-Pad2)") (class "Default")
      (node (ref "M7") (pin "2") (pinfunction "2_2") (pintype "passive"))
    )
    (net (code "86") (name "unconnected-(M8-Pad2)") (class "Default")
      (node (ref "M8") (pin "2") (pinfunction "2_2") (pintype "passive"))
    )
    (net (code "87") (name "unconnected-(MOLEX_105164-0001-ID-Pad4)") (class "Default")
      (node (ref "MOLEX_105164-0001") (pin "4") (pinfunction "ID_4") (pintype "passive"))
    )
    (net (code "88") (name "unconnected-(U4-RS-Pad8)") (class "Default")
      (node (ref "U4") (pin "8") (pinfunction "RS_8") (pintype "bidirectional"))
    )
    (net (code "89") (name "unconnected-(U4-VREF-Pad5)") (class "Default")
      (node (ref "U4") (pin "5") (pinfunction "VREF_5") (pintype "bidirectional"))
    )
  )
)
